# placa1.net
KiCad netlist of a schematic drawn in EAGLE
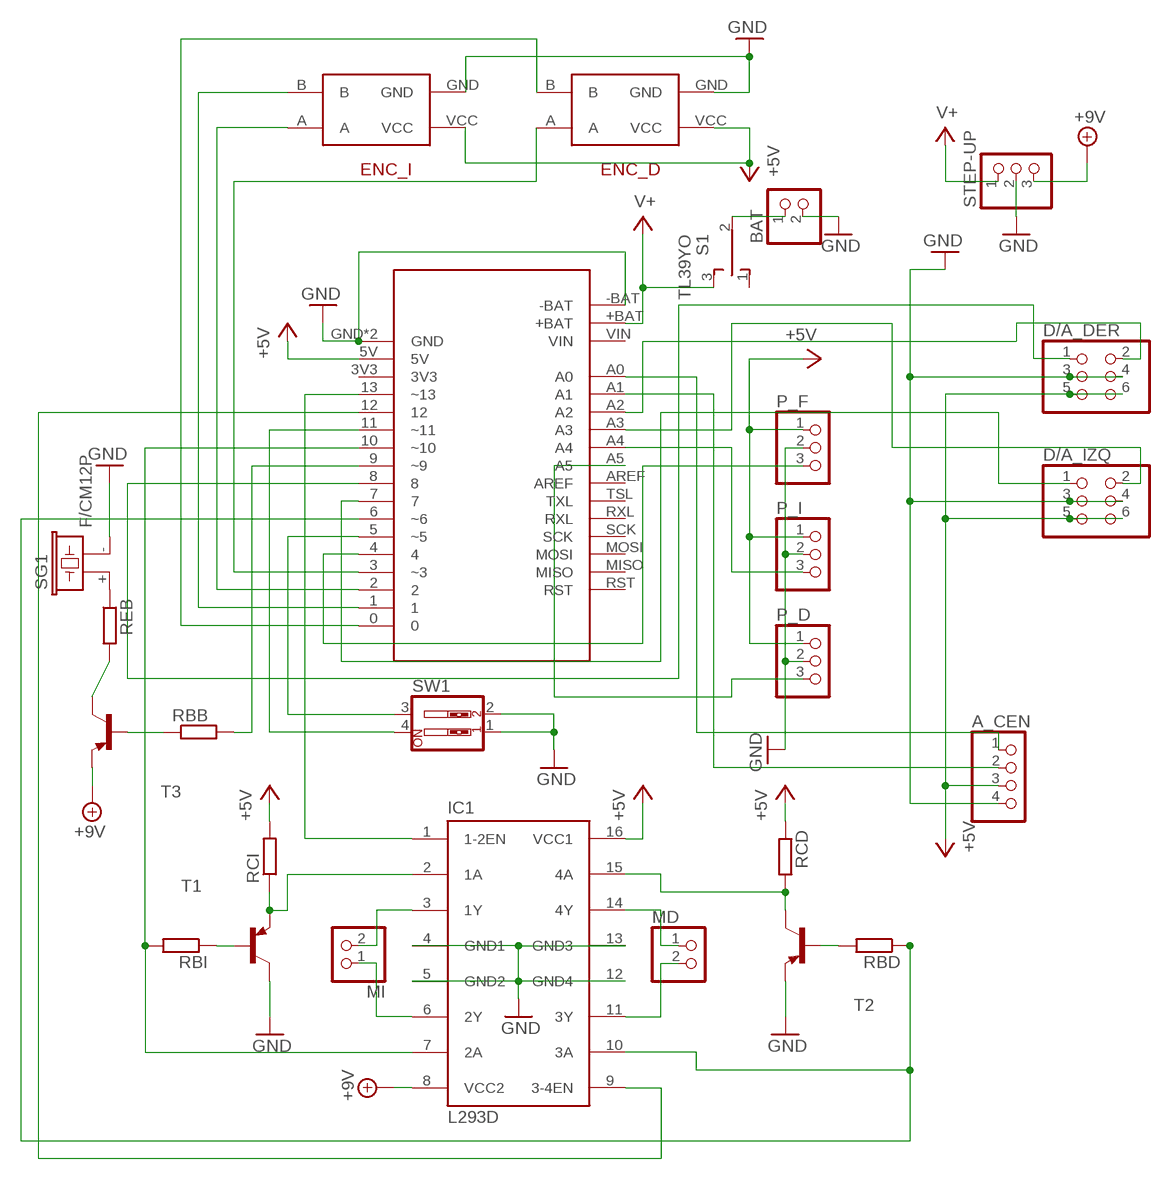
[diagram p0: schematic, sheet 1]

(export (version "E")
  (design (tool "Eeschema 10.0.6"))
  (components
    (comp (ref "A_CEN")
      (value "PINHD-1X4/90")
      (footprint "eagle-import:1X04_90")
      (libsource (lib "eagle-import") (part "PINHD-1X4/90"))
    )
    (comp (ref "BAT")
      (value "PINHD-1X2")
      (footprint "eagle-import:1X02")
      (libsource (lib "eagle-import") (part "PINHD-1X2"))
    )
    (comp (ref "D/A_DER")
      (value "PINHD-2X3/90")
      (footprint "eagle-import:2X03_90")
      (libsource (lib "eagle-import") (part "PINHD-2X3/90"))
    )
    (comp (ref "D/A_IZQ")
      (value "PINHD-2X3/90")
      (footprint "eagle-import:2X03_90")
      (libsource (lib "eagle-import") (part "PINHD-2X3/90"))
    )
    (comp (ref "ENC_D")
      (value "POLOLU_ENCODER")
      (footprint "eagle-import:POLOLU_ENCODER")
      (libsource (lib "eagle-import") (part "POLOLU_ENCODER"))
    )
    (comp (ref "ENC_I")
      (value "POLOLU_ENCODER")
      (footprint "eagle-import:POLOLU_ENCODER")
      (libsource (lib "eagle-import") (part "POLOLU_ENCODER"))
    )
    (comp (ref "IC1")
      (value "L293D")
      (footprint "eagle-import:DIL16")
      (libsource (lib "eagle-import") (part "L293D"))
    )
    (comp (ref "MD")
      (value "PINHD-1X2")
      (footprint "eagle-import:1X02")
      (libsource (lib "eagle-import") (part "PINHD-1X2"))
    )
    (comp (ref "MI")
      (value "PINHD-1X2")
      (footprint "eagle-import:1X02")
      (libsource (lib "eagle-import") (part "PINHD-1X2"))
    )
    (comp (ref "P_D")
      (value "PINHD-1X3/90")
      (footprint "eagle-import:1X03_90")
      (libsource (lib "eagle-import") (part "PINHD-1X3/90"))
    )
    (comp (ref "P_F")
      (value "PINHD-1X3")
      (footprint "eagle-import:1X03")
      (libsource (lib "eagle-import") (part "PINHD-1X3"))
    )
    (comp (ref "P_I")
      (value "PINHD-1X3/90")
      (footprint "eagle-import:1X03_90")
      (libsource (lib "eagle-import") (part "PINHD-1X3/90"))
    )
    (comp (ref "RBB")
      (value "R0204/7")
      (footprint "eagle-import:0204_7")
      (libsource (lib "eagle-import") (part "R0204/7"))
    )
    (comp (ref "RBD")
      (value "R0204/7")
      (footprint "eagle-import:0204_7")
      (libsource (lib "eagle-import") (part "R0204/7"))
    )
    (comp (ref "RBI")
      (value "R0204/7")
      (footprint "eagle-import:0204_7")
      (libsource (lib "eagle-import") (part "R0204/7"))
    )
    (comp (ref "RCD")
      (value "R0204/7")
      (footprint "eagle-import:0204_7")
      (libsource (lib "eagle-import") (part "R0204/7"))
    )
    (comp (ref "RCI")
      (value "R0204/7")
      (footprint "eagle-import:0204_7")
      (libsource (lib "eagle-import") (part "R0204/7"))
    )
    (comp (ref "REB")
      (value "R0204/7")
      (footprint "eagle-import:0204_7")
      (libsource (lib "eagle-import") (part "R0204/7"))
    )
    (comp (ref "S1")
      (value "TL39YO")
      (footprint "eagle-import:TL3XYO")
      (libsource (lib "eagle-import") (part "TL39YO"))
    )
    (comp (ref "SG1")
      (value "F/CM12P")
      (footprint "eagle-import:F_CM12P")
      (libsource (lib "eagle-import") (part "F/CM12P"))
    )
    (comp (ref "STEP-UP")
      (value "PINHD-1X3")
      (footprint "eagle-import:1X03")
      (libsource (lib "eagle-import") (part "PINHD-1X3"))
    )
    (comp (ref "SW1")
      (value "SW_DIP-2")
      (footprint "eagle-import:EDG-02")
      (libsource (lib "eagle-import") (part "SW_DIP-2"))
    )
    (comp (ref "T1")
      (value "-PNP-TO92-BEC")
      (footprint "eagle-import:TO92-BEC")
      (libsource (lib "eagle-import") (part "-PNP-TO92-BEC"))
    )
    (comp (ref "T2")
      (value "-PNP-TO92-BEC")
      (footprint "eagle-import:TO92-BEC")
      (libsource (lib "eagle-import") (part "-PNP-TO92-BEC"))
    )
    (comp (ref "T3")
      (value "-PNP-TO92-BEC")
      (footprint "eagle-import:TO92-BEC")
      (libsource (lib "eagle-import") (part "-PNP-TO92-BEC"))
    )
    (comp (ref "U$1")
      (value "A-STAR_LV")
      (footprint "eagle-import:A-STAR_LV")
      (libsource (lib "eagle-import") (part "A-STAR_LV"))
    )
  )
  (nets
    (net (code "1") (name "+5V") (class "Default")
      (node (ref "A_CEN") (pin "3") (pinfunction "3_3") (pintype "passive"))
      (node (ref "D/A_DER") (pin "5") (pinfunction "5_5") (pintype "passive"))
      (node (ref "D/A_DER") (pin "6") (pinfunction "6_6") (pintype "passive"))
      (node (ref "D/A_IZQ") (pin "5") (pinfunction "5_5") (pintype "passive"))
      (node (ref "D/A_IZQ") (pin "6") (pinfunction "6_6") (pintype "passive"))
      (node (ref "ENC_D") (pin "VCC") (pinfunction "VCC_VCC") (pintype "bidirectional"))
      (node (ref "ENC_I") (pin "VCC") (pinfunction "VCC_VCC") (pintype "bidirectional"))
      (node (ref "IC1") (pin "16") (pinfunction "VCC1_16") (pintype "power_in"))
      (node (ref "P_D") (pin "1") (pinfunction "1_1") (pintype "passive"))
      (node (ref "P_F") (pin "1") (pinfunction "1_1") (pintype "passive"))
      (node (ref "P_I") (pin "1") (pinfunction "1_1") (pintype "passive"))
      (node (ref "RCD") (pin "1") (pinfunction "1_1") (pintype "passive"))
      (node (ref "RCI") (pin "2") (pinfunction "2_2") (pintype "passive"))
      (node (ref "U$1") (pin "5V") (pinfunction "5V_5V") (pintype "bidirectional"))
    )
    (net (code "2") (name "+9V") (class "Default")
      (node (ref "IC1") (pin "8") (pinfunction "VCC2_8") (pintype "power_in"))
      (node (ref "STEP-UP") (pin "3") (pinfunction "3_3") (pintype "passive"))
      (node (ref "T3") (pin "E") (pinfunction "E_E") (pintype "passive"))
    )
    (net (code "3") (name "GND") (class "Default")
      (node (ref "A_CEN") (pin "4") (pinfunction "4_4") (pintype "passive"))
      (node (ref "BAT") (pin "2") (pinfunction "2_2") (pintype "passive"))
      (node (ref "D/A_DER") (pin "3") (pinfunction "3_3") (pintype "passive"))
      (node (ref "D/A_DER") (pin "4") (pinfunction "4_4") (pintype "passive"))
      (node (ref "D/A_IZQ") (pin "3") (pinfunction "3_3") (pintype "passive"))
      (node (ref "D/A_IZQ") (pin "4") (pinfunction "4_4") (pintype "passive"))
      (node (ref "ENC_D") (pin "GND") (pinfunction "GND_GND") (pintype "bidirectional"))
      (node (ref "ENC_I") (pin "GND") (pinfunction "GND_GND") (pintype "bidirectional"))
      (node (ref "IC1") (pin "12") (pinfunction "GND4_12") (pintype "power_in"))
      (node (ref "IC1") (pin "13") (pinfunction "GND3_13") (pintype "power_in"))
      (node (ref "IC1") (pin "4") (pinfunction "GND1_4") (pintype "power_in"))
      (node (ref "IC1") (pin "5") (pinfunction "GND2_5") (pintype "power_in"))
      (node (ref "P_D") (pin "2") (pinfunction "2_2") (pintype "passive"))
      (node (ref "P_F") (pin "2") (pinfunction "2_2") (pintype "passive"))
      (node (ref "P_I") (pin "2") (pinfunction "2_2") (pintype "passive"))
      (node (ref "SG1") (pin "-") (pinfunction "2_-") (pintype "passive"))
      (node (ref "STEP-UP") (pin "2") (pinfunction "2_2") (pintype "passive"))
      (node (ref "SW1") (pin "1") (pinfunction "1_1") (pintype "passive"))
      (node (ref "SW1") (pin "2") (pinfunction "2_2") (pintype "passive"))
      (node (ref "T1") (pin "C") (pinfunction "C_C") (pintype "passive"))
      (node (ref "T2") (pin "E") (pinfunction "E_E") (pintype "passive"))
      (node (ref "U$1") (pin "-BAT") (pinfunction "-BAT_-BAT") (pintype "bidirectional"))
      (node (ref "U$1") (pin "GND") (pinfunction "GND_GND") (pintype "bidirectional"))
      (node (ref "U$1") (pin "GND2") (pinfunction "GND_GND2") (pintype "bidirectional"))
    )
    (net (code "4") (name "Net-(A_CEN-Pad1)") (class "Default")
      (node (ref "A_CEN") (pin "1") (pinfunction "1_1") (pintype "passive"))
      (node (ref "U$1") (pin "A0") (pinfunction "A0_A0") (pintype "bidirectional"))
    )
    (net (code "5") (name "Net-(A_CEN-Pad2)") (class "Default")
      (node (ref "A_CEN") (pin "2") (pinfunction "2_2") (pintype "passive"))
      (node (ref "U$1") (pin "A1") (pinfunction "A1_A1") (pintype "bidirectional"))
    )
    (net (code "6") (name "Net-(D/A_DER-Pad1)") (class "Default")
      (node (ref "D/A_DER") (pin "1") (pinfunction "1_1") (pintype "passive"))
      (node (ref "U$1") (pin "8") (pinfunction "8_8") (pintype "bidirectional"))
    )
    (net (code "7") (name "Net-(D/A_DER-Pad2)") (class "Default")
      (node (ref "D/A_DER") (pin "2") (pinfunction "2_2") (pintype "passive"))
      (node (ref "U$1") (pin "A2") (pinfunction "A2_A2") (pintype "bidirectional"))
    )
    (net (code "8") (name "Net-(D/A_IZQ-Pad1)") (class "Default")
      (node (ref "D/A_IZQ") (pin "1") (pinfunction "1_1") (pintype "passive"))
      (node (ref "U$1") (pin "7") (pinfunction "7_7") (pintype "bidirectional"))
    )
    (net (code "9") (name "Net-(D/A_IZQ-Pad2)") (class "Default")
      (node (ref "D/A_IZQ") (pin "2") (pinfunction "2_2") (pintype "passive"))
      (node (ref "U$1") (pin "A3") (pinfunction "A3_A3") (pintype "bidirectional"))
    )
    (net (code "10") (name "Net-(ENC_D-PadB)") (class "Default")
      (node (ref "ENC_D") (pin "B") (pinfunction "B_B") (pintype "bidirectional"))
      (node (ref "U$1") (pin "0") (pinfunction "0_0") (pintype "bidirectional"))
    )
    (net (code "11") (name "Net-(ENC_I-PadA)") (class "Default")
      (node (ref "ENC_I") (pin "A") (pinfunction "A_A") (pintype "bidirectional"))
      (node (ref "U$1") (pin "2") (pinfunction "2_2") (pintype "bidirectional"))
    )
    (net (code "12") (name "Net-(ENC_I-PadB)") (class "Default")
      (node (ref "ENC_I") (pin "B") (pinfunction "B_B") (pintype "bidirectional"))
      (node (ref "U$1") (pin "1") (pinfunction "1_1") (pintype "bidirectional"))
    )
    (net (code "13") (name "Net-(IC1-1-2EN)") (class "Default")
      (node (ref "IC1") (pin "1") (pinfunction "1-2EN_1") (pintype "input"))
      (node (ref "U$1") (pin "13") (pinfunction "~{13}_13") (pintype "bidirectional"))
    )
    (net (code "14") (name "Net-(IC1-1A)") (class "Default")
      (node (ref "IC1") (pin "2") (pinfunction "1A_2") (pintype "input"))
      (node (ref "RCI") (pin "1") (pinfunction "1_1") (pintype "passive"))
      (node (ref "T1") (pin "E") (pinfunction "E_E") (pintype "passive"))
    )
    (net (code "15") (name "Net-(IC1-1Y)") (class "Default")
      (node (ref "IC1") (pin "3") (pinfunction "1Y_3") (pintype "output"))
      (node (ref "MI") (pin "2") (pinfunction "2_2") (pintype "passive"))
    )
    (net (code "16") (name "Net-(IC1-2A)") (class "Default")
      (node (ref "IC1") (pin "7") (pinfunction "2A_7") (pintype "input"))
      (node (ref "RBI") (pin "2") (pinfunction "2_2") (pintype "passive"))
      (node (ref "U$1") (pin "10") (pinfunction "~{10}_10") (pintype "bidirectional"))
    )
    (net (code "17") (name "Net-(IC1-2Y)") (class "Default")
      (node (ref "IC1") (pin "6") (pinfunction "2Y_6") (pintype "output"))
      (node (ref "MI") (pin "1") (pinfunction "1_1") (pintype "passive"))
    )
    (net (code "18") (name "Net-(IC1-3-4EN)") (class "Default")
      (node (ref "IC1") (pin "9") (pinfunction "3-4EN_9") (pintype "input"))
      (node (ref "U$1") (pin "12") (pinfunction "12_12") (pintype "bidirectional"))
    )
    (net (code "19") (name "Net-(IC1-3A)") (class "Default")
      (node (ref "IC1") (pin "10") (pinfunction "3A_10") (pintype "input"))
      (node (ref "RBD") (pin "1") (pinfunction "1_1") (pintype "passive"))
      (node (ref "U$1") (pin "6") (pinfunction "~{6}_6") (pintype "bidirectional"))
    )
    (net (code "20") (name "Net-(IC1-3Y)") (class "Default")
      (node (ref "IC1") (pin "11") (pinfunction "3Y_11") (pintype "output"))
      (node (ref "MD") (pin "2") (pinfunction "2_2") (pintype "passive"))
    )
    (net (code "21") (name "Net-(IC1-4A)") (class "Default")
      (node (ref "IC1") (pin "15") (pinfunction "4A_15") (pintype "input"))
      (node (ref "RCD") (pin "2") (pinfunction "2_2") (pintype "passive"))
      (node (ref "T2") (pin "C") (pinfunction "C_C") (pintype "passive"))
    )
    (net (code "22") (name "Net-(IC1-4Y)") (class "Default")
      (node (ref "IC1") (pin "14") (pinfunction "4Y_14") (pintype "output"))
      (node (ref "MD") (pin "1") (pinfunction "1_1") (pintype "passive"))
    )
    (net (code "23") (name "Net-(P_D-Pad3)") (class "Default")
      (node (ref "P_D") (pin "3") (pinfunction "3_3") (pintype "passive"))
      (node (ref "U$1") (pin "A5") (pinfunction "A5_A5") (pintype "bidirectional"))
    )
    (net (code "24") (name "Net-(P_F-Pad3)") (class "Default")
      (node (ref "P_F") (pin "3") (pinfunction "3_3") (pintype "passive"))
      (node (ref "U$1") (pin "4") (pinfunction "4_4") (pintype "bidirectional"))
    )
    (net (code "25") (name "Net-(P_I-Pad3)") (class "Default")
      (node (ref "P_I") (pin "3") (pinfunction "3_3") (pintype "passive"))
      (node (ref "U$1") (pin "A4") (pinfunction "A4_A4") (pintype "bidirectional"))
    )
    (net (code "26") (name "Net-(RBB-Pad1)") (class "Default")
      (node (ref "RBB") (pin "1") (pinfunction "1_1") (pintype "passive"))
      (node (ref "T3") (pin "B") (pinfunction "B_B") (pintype "passive"))
    )
    (net (code "27") (name "Net-(RBD-Pad2)") (class "Default")
      (node (ref "RBD") (pin "2") (pinfunction "2_2") (pintype "passive"))
      (node (ref "T2") (pin "B") (pinfunction "B_B") (pintype "passive"))
    )
    (net (code "28") (name "Net-(RBI-Pad1)") (class "Default")
      (node (ref "RBI") (pin "1") (pinfunction "1_1") (pintype "passive"))
      (node (ref "T1") (pin "B") (pinfunction "B_B") (pintype "passive"))
    )
    (net (code "29") (name "Net-(REB-Pad2)") (class "Default")
      (node (ref "REB") (pin "2") (pinfunction "2_2") (pintype "passive"))
      (node (ref "T3") (pin "C") (pinfunction "C_C") (pintype "passive"))
    )
    (net (code "30") (name "Net-(S1-P)") (class "Default")
      (node (ref "BAT") (pin "1") (pinfunction "1_1") (pintype "passive"))
      (node (ref "S1") (pin "2") (pinfunction "P_2") (pintype "passive"))
    )
    (net (code "31") (name "Net-(SG1-1)") (class "Default")
      (node (ref "REB") (pin "1") (pinfunction "1_1") (pintype "passive"))
      (node (ref "SG1") (pin "+") (pinfunction "1_+") (pintype "passive"))
    )
    (net (code "32") (name "Net-(U$1-~{3})") (class "Default")
      (node (ref "ENC_D") (pin "A") (pinfunction "A_A") (pintype "bidirectional"))
      (node (ref "U$1") (pin "3") (pinfunction "~{3}_3") (pintype "bidirectional"))
    )
    (net (code "33") (name "Net-(U$1-~{5})") (class "Default")
      (node (ref "SW1") (pin "3") (pinfunction "3_3") (pintype "passive"))
      (node (ref "U$1") (pin "5") (pinfunction "~{5}_5") (pintype "bidirectional"))
    )
    (net (code "34") (name "Net-(U$1-~{9})") (class "Default")
      (node (ref "RBB") (pin "2") (pinfunction "2_2") (pintype "passive"))
      (node (ref "U$1") (pin "9") (pinfunction "~{9}_9") (pintype "bidirectional"))
    )
    (net (code "35") (name "Net-(U$1-~{11})") (class "Default")
      (node (ref "SW1") (pin "4") (pinfunction "4_4") (pintype "passive"))
      (node (ref "U$1") (pin "11") (pinfunction "~{11}_11") (pintype "bidirectional"))
    )
    (net (code "36") (name "V+") (class "Default")
      (node (ref "S1") (pin "3") (pinfunction "S_3") (pintype "passive"))
      (node (ref "STEP-UP") (pin "1") (pinfunction "1_1") (pintype "passive"))
      (node (ref "U$1") (pin "+BAT") (pinfunction "+BAT_+BAT") (pintype "bidirectional"))
    )
    (net (code "37") (name "unconnected-(S1-O-Pad1)") (class "Default")
      (node (ref "S1") (pin "1") (pinfunction "O_1") (pintype "passive"))
    )
    (net (code "38") (name "unconnected-(U$1-Pad3V3)") (class "Default")
      (node (ref "U$1") (pin "3V3") (pinfunction "3V3_3V3") (pintype "bidirectional"))
    )
    (net (code "39") (name "unconnected-(U$1-PadAREF)") (class "Default")
      (node (ref "U$1") (pin "AREF") (pinfunction "AREF_AREF") (pintype "bidirectional"))
    )
    (net (code "40") (name "unconnected-(U$1-PadMISO)") (class "Default")
      (node (ref "U$1") (pin "MISO") (pinfunction "MISO_MISO") (pintype "bidirectional"))
    )
    (net (code "41") (name "unconnected-(U$1-PadMOSI)") (class "Default")
      (node (ref "U$1") (pin "MOSI") (pinfunction "MOSI_MOSI") (pintype "bidirectional"))
    )
    (net (code "42") (name "unconnected-(U$1-PadRST)") (class "Default")
      (node (ref "U$1") (pin "RST") (pinfunction "RST_RST") (pintype "bidirectional"))
    )
    (net (code "43") (name "unconnected-(U$1-PadRXL)") (class "Default")
      (node (ref "U$1") (pin "RXL") (pinfunction "RXL_RXL") (pintype "bidirectional"))
    )
    (net (code "44") (name "unconnected-(U$1-PadSCK)") (class "Default")
      (node (ref "U$1") (pin "SCK") (pinfunction "SCK_SCK") (pintype "bidirectional"))
    )
    (net (code "45") (name "unconnected-(U$1-PadVIN)") (class "Default")
      (node (ref "U$1") (pin "VIN") (pinfunction "VIN_VIN") (pintype "bidirectional"))
    )
    (net (code "46") (name "unconnected-(U$1-TXL-PadTSL)") (class "Default")
      (node (ref "U$1") (pin "TSL") (pinfunction "TXL_TSL") (pintype "bidirectional"))
    )
  )
)
